# tix_display.net
KiCad netlist of a schematic drawn in EAGLE
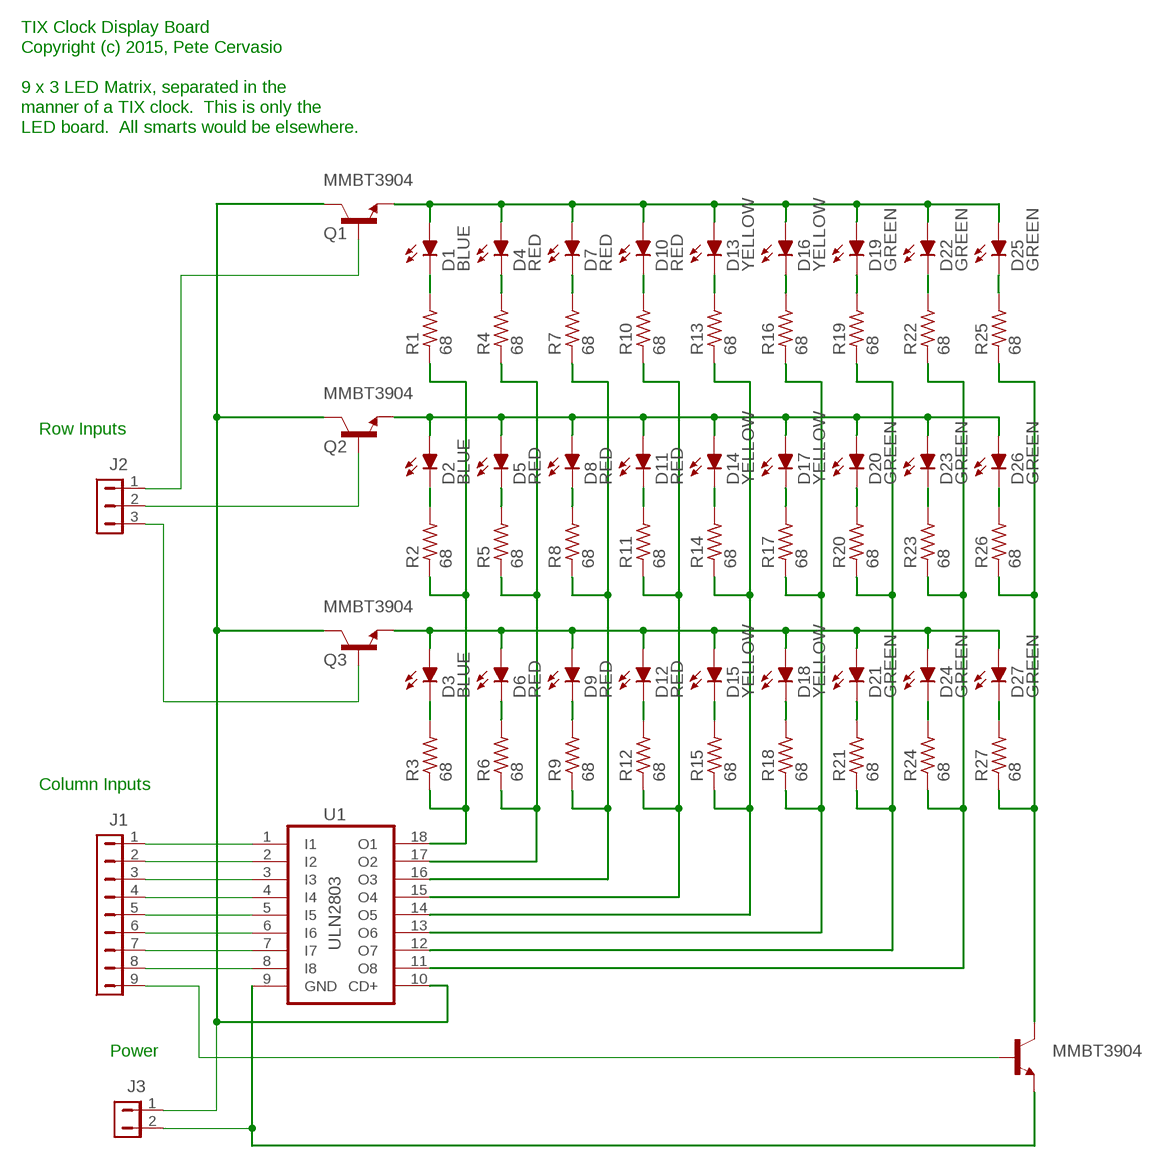
[diagram p0: schematic, sheet 1]

(export (version "E")
  (design (tool "Eeschema 10.0.6"))
  (components
    (comp (ref "D1")
      (value "BLUE")
      (footprint "eagle-import:AA2214SURSK")
      (libsource (lib "eagle-import") (part "AA2214SURSK"))
    )
    (comp (ref "D2")
      (value "BLUE")
      (footprint "eagle-import:AA2214SURSK")
      (libsource (lib "eagle-import") (part "AA2214SURSK"))
    )
    (comp (ref "D3")
      (value "BLUE")
      (footprint "eagle-import:AA2214SURSK")
      (libsource (lib "eagle-import") (part "AA2214SURSK"))
    )
    (comp (ref "D4")
      (value "RED")
      (footprint "eagle-import:AA2214SURSK")
      (libsource (lib "eagle-import") (part "AA2214SURSK"))
    )
    (comp (ref "D5")
      (value "RED")
      (footprint "eagle-import:AA2214SURSK")
      (libsource (lib "eagle-import") (part "AA2214SURSK"))
    )
    (comp (ref "D6")
      (value "RED")
      (footprint "eagle-import:AA2214SURSK")
      (libsource (lib "eagle-import") (part "AA2214SURSK"))
    )
    (comp (ref "D7")
      (value "RED")
      (footprint "eagle-import:AA2214SURSK")
      (libsource (lib "eagle-import") (part "AA2214SURSK"))
    )
    (comp (ref "D8")
      (value "RED")
      (footprint "eagle-import:AA2214SURSK")
      (libsource (lib "eagle-import") (part "AA2214SURSK"))
    )
    (comp (ref "D9")
      (value "RED")
      (footprint "eagle-import:AA2214SURSK")
      (libsource (lib "eagle-import") (part "AA2214SURSK"))
    )
    (comp (ref "D10")
      (value "RED")
      (footprint "eagle-import:AA2214SURSK")
      (libsource (lib "eagle-import") (part "AA2214SURSK"))
    )
    (comp (ref "D11")
      (value "RED")
      (footprint "eagle-import:AA2214SURSK")
      (libsource (lib "eagle-import") (part "AA2214SURSK"))
    )
    (comp (ref "D12")
      (value "RED")
      (footprint "eagle-import:AA2214SURSK")
      (libsource (lib "eagle-import") (part "AA2214SURSK"))
    )
    (comp (ref "D13")
      (value "YELLOW")
      (footprint "eagle-import:AA2214SURSK")
      (libsource (lib "eagle-import") (part "AA2214SURSK"))
    )
    (comp (ref "D14")
      (value "YELLOW")
      (footprint "eagle-import:AA2214SURSK")
      (libsource (lib "eagle-import") (part "AA2214SURSK"))
    )
    (comp (ref "D15")
      (value "YELLOW")
      (footprint "eagle-import:AA2214SURSK")
      (libsource (lib "eagle-import") (part "AA2214SURSK"))
    )
    (comp (ref "D16")
      (value "YELLOW")
      (footprint "eagle-import:AA2214SURSK")
      (libsource (lib "eagle-import") (part "AA2214SURSK"))
    )
    (comp (ref "D17")
      (value "YELLOW")
      (footprint "eagle-import:AA2214SURSK")
      (libsource (lib "eagle-import") (part "AA2214SURSK"))
    )
    (comp (ref "D18")
      (value "YELLOW")
      (footprint "eagle-import:AA2214SURSK")
      (libsource (lib "eagle-import") (part "AA2214SURSK"))
    )
    (comp (ref "D19")
      (value "GREEN")
      (footprint "eagle-import:AA2214SURSK")
      (libsource (lib "eagle-import") (part "AA2214SURSK"))
    )
    (comp (ref "D20")
      (value "GREEN")
      (footprint "eagle-import:AA2214SURSK")
      (libsource (lib "eagle-import") (part "AA2214SURSK"))
    )
    (comp (ref "D21")
      (value "GREEN")
      (footprint "eagle-import:AA2214SURSK")
      (libsource (lib "eagle-import") (part "AA2214SURSK"))
    )
    (comp (ref "D22")
      (value "GREEN")
      (footprint "eagle-import:AA2214SURSK")
      (libsource (lib "eagle-import") (part "AA2214SURSK"))
    )
    (comp (ref "D23")
      (value "GREEN")
      (footprint "eagle-import:AA2214SURSK")
      (libsource (lib "eagle-import") (part "AA2214SURSK"))
    )
    (comp (ref "D24")
      (value "GREEN")
      (footprint "eagle-import:AA2214SURSK")
      (libsource (lib "eagle-import") (part "AA2214SURSK"))
    )
    (comp (ref "D25")
      (value "GREEN")
      (footprint "eagle-import:AA2214SURSK")
      (libsource (lib "eagle-import") (part "AA2214SURSK"))
    )
    (comp (ref "D26")
      (value "GREEN")
      (footprint "eagle-import:AA2214SURSK")
      (libsource (lib "eagle-import") (part "AA2214SURSK"))
    )
    (comp (ref "D27")
      (value "GREEN")
      (footprint "eagle-import:AA2214SURSK")
      (libsource (lib "eagle-import") (part "AA2214SURSK"))
    )
    (comp (ref "J1")
      (value "MTA09-100")
      (footprint "eagle-import:MTA09-100")
      (libsource (lib "eagle-import") (part "MTA09-100"))
    )
    (comp (ref "J2")
      (value "MTA03-100")
      (footprint "eagle-import:MTA03-100")
      (libsource (lib "eagle-import") (part "MTA03-100"))
    )
    (comp (ref "J3")
      (value "MTA02-100")
      (footprint "eagle-import:MTA02-100")
      (libsource (lib "eagle-import") (part "MTA02-100"))
    )
    (comp (ref "Q1")
      (value "MMBT3904")
      (footprint "eagle-import:SOT23-BEC")
      (libsource (lib "eagle-import") (part "MMBT3904"))
    )
    (comp (ref "Q2")
      (value "MMBT3904")
      (footprint "eagle-import:SOT23-BEC")
      (libsource (lib "eagle-import") (part "MMBT3904"))
    )
    (comp (ref "Q3")
      (value "MMBT3904")
      (footprint "eagle-import:SOT23-BEC")
      (libsource (lib "eagle-import") (part "MMBT3904"))
    )
    (comp (ref "Q4")
      (value "MMBT3904")
      (footprint "eagle-import:SOT23-BEC")
      (libsource (lib "eagle-import") (part "MMBT3904"))
    )
    (comp (ref "R1")
      (value "68")
      (footprint "eagle-import:M0805")
      (libsource (lib "eagle-import") (part "R-US_M0805"))
    )
    (comp (ref "R2")
      (value "68")
      (footprint "eagle-import:M0805")
      (libsource (lib "eagle-import") (part "R-US_M0805"))
    )
    (comp (ref "R3")
      (value "68")
      (footprint "eagle-import:M0805")
      (libsource (lib "eagle-import") (part "R-US_M0805"))
    )
    (comp (ref "R4")
      (value "68")
      (footprint "eagle-import:M0805")
      (libsource (lib "eagle-import") (part "R-US_M0805"))
    )
    (comp (ref "R5")
      (value "68")
      (footprint "eagle-import:M0805")
      (libsource (lib "eagle-import") (part "R-US_M0805"))
    )
    (comp (ref "R6")
      (value "68")
      (footprint "eagle-import:M0805")
      (libsource (lib "eagle-import") (part "R-US_M0805"))
    )
    (comp (ref "R7")
      (value "68")
      (footprint "eagle-import:M0805")
      (libsource (lib "eagle-import") (part "R-US_M0805"))
    )
    (comp (ref "R8")
      (value "68")
      (footprint "eagle-import:M0805")
      (libsource (lib "eagle-import") (part "R-US_M0805"))
    )
    (comp (ref "R9")
      (value "68")
      (footprint "eagle-import:M0805")
      (libsource (lib "eagle-import") (part "R-US_M0805"))
    )
    (comp (ref "R10")
      (value "68")
      (footprint "eagle-import:M0805")
      (libsource (lib "eagle-import") (part "R-US_M0805"))
    )
    (comp (ref "R11")
      (value "68")
      (footprint "eagle-import:M0805")
      (libsource (lib "eagle-import") (part "R-US_M0805"))
    )
    (comp (ref "R12")
      (value "68")
      (footprint "eagle-import:M0805")
      (libsource (lib "eagle-import") (part "R-US_M0805"))
    )
    (comp (ref "R13")
      (value "68")
      (footprint "eagle-import:M0805")
      (libsource (lib "eagle-import") (part "R-US_M0805"))
    )
    (comp (ref "R14")
      (value "68")
      (footprint "eagle-import:M0805")
      (libsource (lib "eagle-import") (part "R-US_M0805"))
    )
    (comp (ref "R15")
      (value "68")
      (footprint "eagle-import:M0805")
      (libsource (lib "eagle-import") (part "R-US_M0805"))
    )
    (comp (ref "R16")
      (value "68")
      (footprint "eagle-import:M0805")
      (libsource (lib "eagle-import") (part "R-US_M0805"))
    )
    (comp (ref "R17")
      (value "68")
      (footprint "eagle-import:M0805")
      (libsource (lib "eagle-import") (part "R-US_M0805"))
    )
    (comp (ref "R18")
      (value "68")
      (footprint "eagle-import:M0805")
      (libsource (lib "eagle-import") (part "R-US_M0805"))
    )
    (comp (ref "R19")
      (value "68")
      (footprint "eagle-import:M0805")
      (libsource (lib "eagle-import") (part "R-US_M0805"))
    )
    (comp (ref "R20")
      (value "68")
      (footprint "eagle-import:M0805")
      (libsource (lib "eagle-import") (part "R-US_M0805"))
    )
    (comp (ref "R21")
      (value "68")
      (footprint "eagle-import:M0805")
      (libsource (lib "eagle-import") (part "R-US_M0805"))
    )
    (comp (ref "R22")
      (value "68")
      (footprint "eagle-import:M0805")
      (libsource (lib "eagle-import") (part "R-US_M0805"))
    )
    (comp (ref "R23")
      (value "68")
      (footprint "eagle-import:M0805")
      (libsource (lib "eagle-import") (part "R-US_M0805"))
    )
    (comp (ref "R24")
      (value "68")
      (footprint "eagle-import:M0805")
      (libsource (lib "eagle-import") (part "R-US_M0805"))
    )
    (comp (ref "R25")
      (value "68")
      (footprint "eagle-import:M0805")
      (libsource (lib "eagle-import") (part "R-US_M0805"))
    )
    (comp (ref "R26")
      (value "68")
      (footprint "eagle-import:M0805")
      (libsource (lib "eagle-import") (part "R-US_M0805"))
    )
    (comp (ref "R27")
      (value "68")
      (footprint "eagle-import:M0805")
      (libsource (lib "eagle-import") (part "R-US_M0805"))
    )
    (comp (ref "U1")
      (value "ULN2803")
      (footprint "eagle-import:SO18W")
      (libsource (lib "eagle-import") (part "ULN2803AFW"))
    )
  )
  (nets
    (net (code "1") (name "Net-(D1-PadA)") (class "Default")
      (node (ref "D1") (pin "A") (pinfunction "A_A") (pintype "passive"))
      (node (ref "D10") (pin "A") (pinfunction "A_A") (pintype "passive"))
      (node (ref "D13") (pin "A") (pinfunction "A_A") (pintype "passive"))
      (node (ref "D16") (pin "A") (pinfunction "A_A") (pintype "passive"))
      (node (ref "D19") (pin "A") (pinfunction "A_A") (pintype "passive"))
      (node (ref "D22") (pin "A") (pinfunction "A_A") (pintype "passive"))
      (node (ref "D25") (pin "A") (pinfunction "A_A") (pintype "passive"))
      (node (ref "D4") (pin "A") (pinfunction "A_A") (pintype "passive"))
      (node (ref "D7") (pin "A") (pinfunction "A_A") (pintype "passive"))
      (node (ref "Q1") (pin "E") (pinfunction "E_E") (pintype "passive"))
    )
    (net (code "2") (name "Net-(D1-PadC)") (class "Default")
      (node (ref "D1") (pin "C") (pinfunction "C_C") (pintype "passive"))
      (node (ref "R1") (pin "2") (pinfunction "2_2") (pintype "passive"))
    )
    (net (code "3") (name "Net-(D2-PadC)") (class "Default")
      (node (ref "D2") (pin "C") (pinfunction "C_C") (pintype "passive"))
      (node (ref "R2") (pin "2") (pinfunction "2_2") (pintype "passive"))
    )
    (net (code "4") (name "Net-(D3-PadC)") (class "Default")
      (node (ref "D3") (pin "C") (pinfunction "C_C") (pintype "passive"))
      (node (ref "R3") (pin "2") (pinfunction "2_2") (pintype "passive"))
    )
    (net (code "5") (name "Net-(D4-PadC)") (class "Default")
      (node (ref "D4") (pin "C") (pinfunction "C_C") (pintype "passive"))
      (node (ref "R4") (pin "2") (pinfunction "2_2") (pintype "passive"))
    )
    (net (code "6") (name "Net-(D5-PadC)") (class "Default")
      (node (ref "D5") (pin "C") (pinfunction "C_C") (pintype "passive"))
      (node (ref "R5") (pin "2") (pinfunction "2_2") (pintype "passive"))
    )
    (net (code "7") (name "Net-(D6-PadC)") (class "Default")
      (node (ref "D6") (pin "C") (pinfunction "C_C") (pintype "passive"))
      (node (ref "R6") (pin "2") (pinfunction "2_2") (pintype "passive"))
    )
    (net (code "8") (name "Net-(D7-PadC)") (class "Default")
      (node (ref "D7") (pin "C") (pinfunction "C_C") (pintype "passive"))
      (node (ref "R7") (pin "2") (pinfunction "2_2") (pintype "passive"))
    )
    (net (code "9") (name "Net-(D8-PadC)") (class "Default")
      (node (ref "D8") (pin "C") (pinfunction "C_C") (pintype "passive"))
      (node (ref "R8") (pin "2") (pinfunction "2_2") (pintype "passive"))
    )
    (net (code "10") (name "Net-(D9-PadC)") (class "Default")
      (node (ref "D9") (pin "C") (pinfunction "C_C") (pintype "passive"))
      (node (ref "R9") (pin "2") (pinfunction "2_2") (pintype "passive"))
    )
    (net (code "11") (name "Net-(D10-PadC)") (class "Default")
      (node (ref "D10") (pin "C") (pinfunction "C_C") (pintype "passive"))
      (node (ref "R10") (pin "2") (pinfunction "2_2") (pintype "passive"))
    )
    (net (code "12") (name "Net-(D11-PadA)") (class "Default")
      (node (ref "D11") (pin "A") (pinfunction "A_A") (pintype "passive"))
      (node (ref "D14") (pin "A") (pinfunction "A_A") (pintype "passive"))
      (node (ref "D17") (pin "A") (pinfunction "A_A") (pintype "passive"))
      (node (ref "D2") (pin "A") (pinfunction "A_A") (pintype "passive"))
      (node (ref "D20") (pin "A") (pinfunction "A_A") (pintype "passive"))
      (node (ref "D23") (pin "A") (pinfunction "A_A") (pintype "passive"))
      (node (ref "D26") (pin "A") (pinfunction "A_A") (pintype "passive"))
      (node (ref "D5") (pin "A") (pinfunction "A_A") (pintype "passive"))
      (node (ref "D8") (pin "A") (pinfunction "A_A") (pintype "passive"))
      (node (ref "Q2") (pin "E") (pinfunction "E_E") (pintype "passive"))
    )
    (net (code "13") (name "Net-(D11-PadC)") (class "Default")
      (node (ref "D11") (pin "C") (pinfunction "C_C") (pintype "passive"))
      (node (ref "R11") (pin "2") (pinfunction "2_2") (pintype "passive"))
    )
    (net (code "14") (name "Net-(D12-PadA)") (class "Default")
      (node (ref "D12") (pin "A") (pinfunction "A_A") (pintype "passive"))
      (node (ref "D15") (pin "A") (pinfunction "A_A") (pintype "passive"))
      (node (ref "D18") (pin "A") (pinfunction "A_A") (pintype "passive"))
      (node (ref "D21") (pin "A") (pinfunction "A_A") (pintype "passive"))
      (node (ref "D24") (pin "A") (pinfunction "A_A") (pintype "passive"))
      (node (ref "D27") (pin "A") (pinfunction "A_A") (pintype "passive"))
      (node (ref "D3") (pin "A") (pinfunction "A_A") (pintype "passive"))
      (node (ref "D6") (pin "A") (pinfunction "A_A") (pintype "passive"))
      (node (ref "D9") (pin "A") (pinfunction "A_A") (pintype "passive"))
      (node (ref "Q3") (pin "E") (pinfunction "E_E") (pintype "passive"))
    )
    (net (code "15") (name "Net-(D12-PadC)") (class "Default")
      (node (ref "D12") (pin "C") (pinfunction "C_C") (pintype "passive"))
      (node (ref "R12") (pin "2") (pinfunction "2_2") (pintype "passive"))
    )
    (net (code "16") (name "Net-(D13-PadC)") (class "Default")
      (node (ref "D13") (pin "C") (pinfunction "C_C") (pintype "passive"))
      (node (ref "R13") (pin "2") (pinfunction "2_2") (pintype "passive"))
    )
    (net (code "17") (name "Net-(D14-PadC)") (class "Default")
      (node (ref "D14") (pin "C") (pinfunction "C_C") (pintype "passive"))
      (node (ref "R14") (pin "2") (pinfunction "2_2") (pintype "passive"))
    )
    (net (code "18") (name "Net-(D15-PadC)") (class "Default")
      (node (ref "D15") (pin "C") (pinfunction "C_C") (pintype "passive"))
      (node (ref "R15") (pin "2") (pinfunction "2_2") (pintype "passive"))
    )
    (net (code "19") (name "Net-(D16-PadC)") (class "Default")
      (node (ref "D16") (pin "C") (pinfunction "C_C") (pintype "passive"))
      (node (ref "R16") (pin "2") (pinfunction "2_2") (pintype "passive"))
    )
    (net (code "20") (name "Net-(D17-PadC)") (class "Default")
      (node (ref "D17") (pin "C") (pinfunction "C_C") (pintype "passive"))
      (node (ref "R17") (pin "2") (pinfunction "2_2") (pintype "passive"))
    )
    (net (code "21") (name "Net-(D18-PadC)") (class "Default")
      (node (ref "D18") (pin "C") (pinfunction "C_C") (pintype "passive"))
      (node (ref "R18") (pin "2") (pinfunction "2_2") (pintype "passive"))
    )
    (net (code "22") (name "Net-(D19-PadC)") (class "Default")
      (node (ref "D19") (pin "C") (pinfunction "C_C") (pintype "passive"))
      (node (ref "R19") (pin "2") (pinfunction "2_2") (pintype "passive"))
    )
    (net (code "23") (name "Net-(D20-PadC)") (class "Default")
      (node (ref "D20") (pin "C") (pinfunction "C_C") (pintype "passive"))
      (node (ref "R20") (pin "2") (pinfunction "2_2") (pintype "passive"))
    )
    (net (code "24") (name "Net-(D21-PadC)") (class "Default")
      (node (ref "D21") (pin "C") (pinfunction "C_C") (pintype "passive"))
      (node (ref "R21") (pin "2") (pinfunction "2_2") (pintype "passive"))
    )
    (net (code "25") (name "Net-(D22-PadC)") (class "Default")
      (node (ref "D22") (pin "C") (pinfunction "C_C") (pintype "passive"))
      (node (ref "R22") (pin "2") (pinfunction "2_2") (pintype "passive"))
    )
    (net (code "26") (name "Net-(D23-PadC)") (class "Default")
      (node (ref "D23") (pin "C") (pinfunction "C_C") (pintype "passive"))
      (node (ref "R23") (pin "2") (pinfunction "2_2") (pintype "passive"))
    )
    (net (code "27") (name "Net-(D24-PadC)") (class "Default")
      (node (ref "D24") (pin "C") (pinfunction "C_C") (pintype "passive"))
      (node (ref "R24") (pin "2") (pinfunction "2_2") (pintype "passive"))
    )
    (net (code "28") (name "Net-(D25-PadC)") (class "Default")
      (node (ref "D25") (pin "C") (pinfunction "C_C") (pintype "passive"))
      (node (ref "R25") (pin "2") (pinfunction "2_2") (pintype "passive"))
    )
    (net (code "29") (name "Net-(D26-PadC)") (class "Default")
      (node (ref "D26") (pin "C") (pinfunction "C_C") (pintype "passive"))
      (node (ref "R26") (pin "2") (pinfunction "2_2") (pintype "passive"))
    )
    (net (code "30") (name "Net-(D27-PadC)") (class "Default")
      (node (ref "D27") (pin "C") (pinfunction "C_C") (pintype "passive"))
      (node (ref "R27") (pin "2") (pinfunction "2_2") (pintype "passive"))
    )
    (net (code "31") (name "Net-(J1-Pad9)") (class "Default")
      (node (ref "J1") (pin "9") (pinfunction "9_9") (pintype "passive"))
      (node (ref "Q4") (pin "B") (pinfunction "B_B") (pintype "passive"))
    )
    (net (code "32") (name "Net-(J2-Pad1)") (class "Default")
      (node (ref "J2") (pin "1") (pinfunction "1_1") (pintype "passive"))
      (node (ref "Q1") (pin "B") (pinfunction "B_B") (pintype "passive"))
    )
    (net (code "33") (name "Net-(J2-Pad2)") (class "Default")
      (node (ref "J2") (pin "2") (pinfunction "2_2") (pintype "passive"))
      (node (ref "Q2") (pin "B") (pinfunction "B_B") (pintype "passive"))
    )
    (net (code "34") (name "Net-(J2-Pad3)") (class "Default")
      (node (ref "J2") (pin "3") (pinfunction "3_3") (pintype "passive"))
      (node (ref "Q3") (pin "B") (pinfunction "B_B") (pintype "passive"))
    )
    (net (code "35") (name "Net-(Q4-PadC)") (class "Default")
      (node (ref "Q4") (pin "C") (pinfunction "C_C") (pintype "passive"))
      (node (ref "R25") (pin "1") (pinfunction "1_1") (pintype "passive"))
      (node (ref "R26") (pin "1") (pinfunction "1_1") (pintype "passive"))
      (node (ref "R27") (pin "1") (pinfunction "1_1") (pintype "passive"))
    )
    (net (code "36") (name "Net-(U1-CD+)") (class "Default")
      (node (ref "J3") (pin "1") (pinfunction "1_1") (pintype "passive"))
      (node (ref "Q1") (pin "C") (pinfunction "C_C") (pintype "passive"))
      (node (ref "Q2") (pin "C") (pinfunction "C_C") (pintype "passive"))
      (node (ref "Q3") (pin "C") (pinfunction "C_C") (pintype "passive"))
      (node (ref "U1") (pin "10") (pinfunction "CD+_10") (pintype "passive"))
    )
    (net (code "37") (name "Net-(U1-GND)") (class "Default")
      (node (ref "J3") (pin "2") (pinfunction "2_2") (pintype "passive"))
      (node (ref "Q4") (pin "E") (pinfunction "E_E") (pintype "passive"))
      (node (ref "U1") (pin "9") (pinfunction "GND_9") (pintype "power_in"))
    )
    (net (code "38") (name "Net-(U1-I1)") (class "Default")
      (node (ref "J1") (pin "1") (pinfunction "1_1") (pintype "passive"))
      (node (ref "U1") (pin "1") (pinfunction "I1_1") (pintype "input"))
    )
    (net (code "39") (name "Net-(U1-I2)") (class "Default")
      (node (ref "J1") (pin "2") (pinfunction "2_2") (pintype "passive"))
      (node (ref "U1") (pin "2") (pinfunction "I2_2") (pintype "input"))
    )
    (net (code "40") (name "Net-(U1-I3)") (class "Default")
      (node (ref "J1") (pin "3") (pinfunction "3_3") (pintype "passive"))
      (node (ref "U1") (pin "3") (pinfunction "I3_3") (pintype "input"))
    )
    (net (code "41") (name "Net-(U1-I4)") (class "Default")
      (node (ref "J1") (pin "4") (pinfunction "4_4") (pintype "passive"))
      (node (ref "U1") (pin "4") (pinfunction "I4_4") (pintype "input"))
    )
    (net (code "42") (name "Net-(U1-I5)") (class "Default")
      (node (ref "J1") (pin "5") (pinfunction "5_5") (pintype "passive"))
      (node (ref "U1") (pin "5") (pinfunction "I5_5") (pintype "input"))
    )
    (net (code "43") (name "Net-(U1-I6)") (class "Default")
      (node (ref "J1") (pin "6") (pinfunction "6_6") (pintype "passive"))
      (node (ref "U1") (pin "6") (pinfunction "I6_6") (pintype "input"))
    )
    (net (code "44") (name "Net-(U1-I7)") (class "Default")
      (node (ref "J1") (pin "7") (pinfunction "7_7") (pintype "passive"))
      (node (ref "U1") (pin "7") (pinfunction "I7_7") (pintype "input"))
    )
    (net (code "45") (name "Net-(U1-I8)") (class "Default")
      (node (ref "J1") (pin "8") (pinfunction "8_8") (pintype "passive"))
      (node (ref "U1") (pin "8") (pinfunction "I8_8") (pintype "input"))
    )
    (net (code "46") (name "Net-(U1-O1)") (class "Default")
      (node (ref "R1") (pin "1") (pinfunction "1_1") (pintype "passive"))
      (node (ref "R2") (pin "1") (pinfunction "1_1") (pintype "passive"))
      (node (ref "R3") (pin "1") (pinfunction "1_1") (pintype "passive"))
      (node (ref "U1") (pin "18") (pinfunction "O1_18") (pintype "open_collector"))
    )
    (net (code "47") (name "Net-(U1-O2)") (class "Default")
      (node (ref "R4") (pin "1") (pinfunction "1_1") (pintype "passive"))
      (node (ref "R5") (pin "1") (pinfunction "1_1") (pintype "passive"))
      (node (ref "R6") (pin "1") (pinfunction "1_1") (pintype "passive"))
      (node (ref "U1") (pin "17") (pinfunction "O2_17") (pintype "open_collector"))
    )
    (net (code "48") (name "Net-(U1-O3)") (class "Default")
      (node (ref "R7") (pin "1") (pinfunction "1_1") (pintype "passive"))
      (node (ref "R8") (pin "1") (pinfunction "1_1") (pintype "passive"))
      (node (ref "R9") (pin "1") (pinfunction "1_1") (pintype "passive"))
      (node (ref "U1") (pin "16") (pinfunction "O3_16") (pintype "open_collector"))
    )
    (net (code "49") (name "Net-(U1-O4)") (class "Default")
      (node (ref "R10") (pin "1") (pinfunction "1_1") (pintype "passive"))
      (node (ref "R11") (pin "1") (pinfunction "1_1") (pintype "passive"))
      (node (ref "R12") (pin "1") (pinfunction "1_1") (pintype "passive"))
      (node (ref "U1") (pin "15") (pinfunction "O4_15") (pintype "open_collector"))
    )
    (net (code "50") (name "Net-(U1-O5)") (class "Default")
      (node (ref "R13") (pin "1") (pinfunction "1_1") (pintype "passive"))
      (node (ref "R14") (pin "1") (pinfunction "1_1") (pintype "passive"))
      (node (ref "R15") (pin "1") (pinfunction "1_1") (pintype "passive"))
      (node (ref "U1") (pin "14") (pinfunction "O5_14") (pintype "open_collector"))
    )
    (net (code "51") (name "Net-(U1-O6)") (class "Default")
      (node (ref "R16") (pin "1") (pinfunction "1_1") (pintype "passive"))
      (node (ref "R17") (pin "1") (pinfunction "1_1") (pintype "passive"))
      (node (ref "R18") (pin "1") (pinfunction "1_1") (pintype "passive"))
      (node (ref "U1") (pin "13") (pinfunction "O6_13") (pintype "open_collector"))
    )
    (net (code "52") (name "Net-(U1-O7)") (class "Default")
      (node (ref "R19") (pin "1") (pinfunction "1_1") (pintype "passive"))
      (node (ref "R20") (pin "1") (pinfunction "1_1") (pintype "passive"))
      (node (ref "R21") (pin "1") (pinfunction "1_1") (pintype "passive"))
      (node (ref "U1") (pin "12") (pinfunction "O7_12") (pintype "open_collector"))
    )
    (net (code "53") (name "Net-(U1-O8)") (class "Default")
      (node (ref "R22") (pin "1") (pinfunction "1_1") (pintype "passive"))
      (node (ref "R23") (pin "1") (pinfunction "1_1") (pintype "passive"))
      (node (ref "R24") (pin "1") (pinfunction "1_1") (pintype "passive"))
      (node (ref "U1") (pin "11") (pinfunction "O8_11") (pintype "open_collector"))
    )
  )
)
